# eBox_Led.net
KiCad netlist of a schematic drawn in Altium Designer
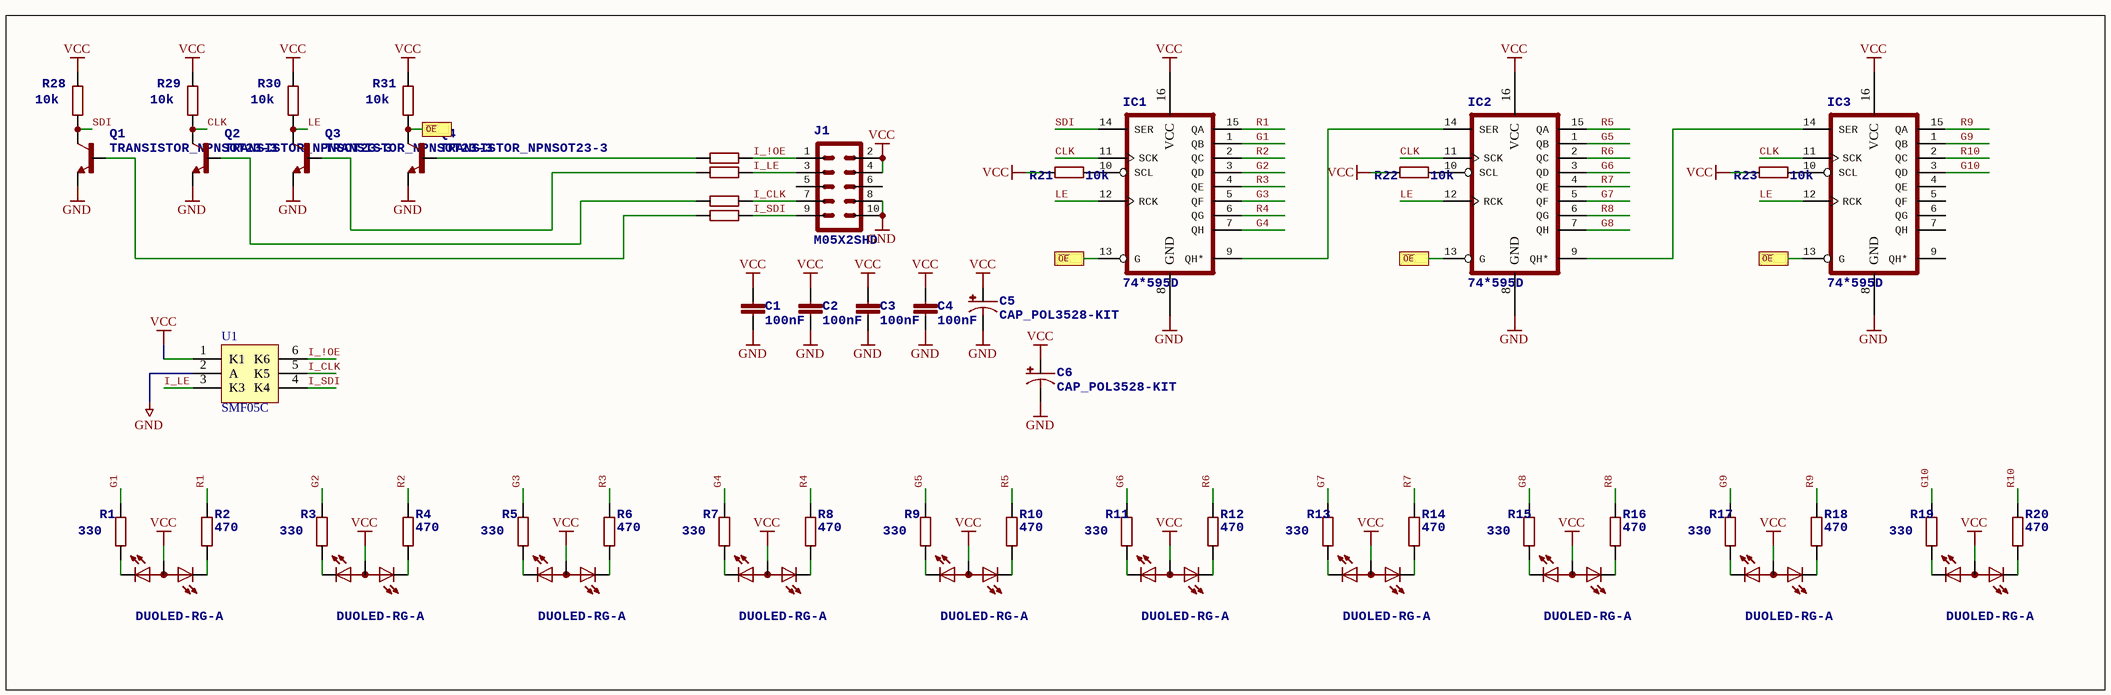
[diagram p0: eBox_Led.SchDoc]

(export (version "E")
  (design (tool "Eeschema 10.0.6"))
  (components
    (comp (ref "C1")
      (value "100nF")
      (footprint "C 0603")
      (description "CapacitorStandard 0603 ceramic capacitor, and 0.1\" leaded capacitor.")
      (libsource (lib "SparkFun-Capacitors") (part "CAP0603-CAP"))
    )
    (comp (ref "C2")
      (value "100nF")
      (footprint "C 0603")
      (description "CapacitorStandard 0603 ceramic capacitor, and 0.1\" leaded capacitor.")
      (libsource (lib "SparkFun-Capacitors") (part "CAP0603-CAP"))
    )
    (comp (ref "C3")
      (value "100nF")
      (footprint "C 0603")
      (description "CapacitorStandard 0603 ceramic capacitor, and 0.1\" leaded capacitor.")
      (libsource (lib "SparkFun-Capacitors") (part "CAP0603-CAP"))
    )
    (comp (ref "C4")
      (value "100nF")
      (footprint "C 0603")
      (description "CapacitorStandard 0603 ceramic capacitor, and 0.1\" leaded capacitor.")
      (libsource (lib "SparkFun-Capacitors") (part "CAP0603-CAP"))
    )
    (comp (ref "C5")
      (value "CAP_POL3528-KIT")
      (footprint "CYL/D.250/LS.100")
      (libsource (lib "SparkFun-Passives") (part "CAP_POL3528-KIT"))
    )
    (comp (ref "C6")
      (value "CAP_POL3528-KIT")
      (footprint "CYL/D.250/LS.100")
      (libsource (lib "SparkFun-Passives") (part "CAP_POL3528-KIT"))
    )
    (comp (ref "IC1")
      (value "74*595D")
      (footprint "SOIC-16")
      (description "8-bit SHIFT REGISTER, output latch")
      (libsource (lib "74xx-eu") (part "74*595D"))
    )
    (comp (ref "IC2")
      (value "74*595D")
      (footprint "SOIC-16")
      (description "8-bit SHIFT REGISTER, output latch")
      (libsource (lib "74xx-eu") (part "74*595D"))
    )
    (comp (ref "IC3")
      (value "74*595D")
      (footprint "SOIC-16")
      (description "8-bit SHIFT REGISTER, output latch")
      (libsource (lib "74xx-eu") (part "74*595D"))
    )
    (comp (ref "J1")
      (value "M05X2SHD")
      (footprint "2X5-SHROUDED")
      (libsource (lib "SparkFun-Connectors") (part "M05X2SHD"))
    )
    (comp (ref "LD1")
      (value "DUOLED-RG-A")
      (footprint "DUOLED-A-5MM")
      (description "DUO LED   2 colors (red/green), 5 mm, round, common Anode www.ligitek.com or other producers.")
      (libsource (lib "led") (part "DUOLED-RG-A"))
    )
    (comp (ref "LD2")
      (value "DUOLED-RG-A")
      (footprint "DUOLED-A-5MM")
      (description "DUO LED   2 colors (red/green), 5 mm, round, common Anode www.ligitek.com or other producers.")
      (libsource (lib "led") (part "DUOLED-RG-A"))
    )
    (comp (ref "LD3")
      (value "DUOLED-RG-A")
      (footprint "DUOLED-A-5MM")
      (description "DUO LED   2 colors (red/green), 5 mm, round, common Anode www.ligitek.com or other producers.")
      (libsource (lib "led") (part "DUOLED-RG-A"))
    )
    (comp (ref "LD4")
      (value "DUOLED-RG-A")
      (footprint "DUOLED-A-5MM")
      (description "DUO LED   2 colors (red/green), 5 mm, round, common Anode www.ligitek.com or other producers.")
      (libsource (lib "led") (part "DUOLED-RG-A"))
    )
    (comp (ref "LD5")
      (value "DUOLED-RG-A")
      (footprint "DUOLED-A-5MM")
      (description "DUO LED   2 colors (red/green), 5 mm, round, common Anode www.ligitek.com or other producers.")
      (libsource (lib "led") (part "DUOLED-RG-A"))
    )
    (comp (ref "LD6")
      (value "DUOLED-RG-A")
      (footprint "DUOLED-A-5MM")
      (description "DUO LED   2 colors (red/green), 5 mm, round, common Anode www.ligitek.com or other producers.")
      (libsource (lib "led") (part "DUOLED-RG-A"))
    )
    (comp (ref "LD7")
      (value "DUOLED-RG-A")
      (footprint "DUOLED-A-5MM")
      (description "DUO LED   2 colors (red/green), 5 mm, round, common Anode www.ligitek.com or other producers.")
      (libsource (lib "led") (part "DUOLED-RG-A"))
    )
    (comp (ref "LD8")
      (value "DUOLED-RG-A")
      (footprint "DUOLED-A-5MM")
      (description "DUO LED   2 colors (red/green), 5 mm, round, common Anode www.ligitek.com or other producers.")
      (libsource (lib "led") (part "DUOLED-RG-A"))
    )
    (comp (ref "LD9")
      (value "DUOLED-RG-A")
      (footprint "DUOLED-A-5MM")
      (description "DUO LED   2 colors (red/green), 5 mm, round, common Anode www.ligitek.com or other producers.")
      (libsource (lib "led") (part "DUOLED-RG-A"))
    )
    (comp (ref "LD10")
      (value "DUOLED-RG-A")
      (footprint "DUOLED-A-5MM")
      (description "DUO LED   2 colors (red/green), 5 mm, round, common Anode www.ligitek.com or other producers.")
      (libsource (lib "led") (part "DUOLED-RG-A"))
    )
    (comp (ref "Q1")
      (value "TRANSISTOR_NPNSOT23-3")
      (footprint "SOT23-3")
      (libsource (lib "SparkFun-DiscreteSemi") (part "TRANSISTOR_NPNSOT23-3"))
    )
    (comp (ref "Q2")
      (value "TRANSISTOR_NPNSOT23-3")
      (footprint "SOT23-3")
      (libsource (lib "SparkFun-DiscreteSemi") (part "TRANSISTOR_NPNSOT23-3"))
    )
    (comp (ref "Q3")
      (value "TRANSISTOR_NPNSOT23-3")
      (footprint "SOT23-3")
      (libsource (lib "SparkFun-DiscreteSemi") (part "TRANSISTOR_NPNSOT23-3"))
    )
    (comp (ref "Q4")
      (value "TRANSISTOR_NPNSOT23-3")
      (footprint "SOT23-3")
      (libsource (lib "SparkFun-DiscreteSemi") (part "TRANSISTOR_NPNSOT23-3"))
    )
    (comp (ref "R1")
      (value "330")
      (footprint "R 0603")
      (description "RESISTOR, European symbol")
      (libsource (lib "rcl") (part "R-EU_R0603"))
    )
    (comp (ref "R2")
      (value "470")
      (footprint "R 0603")
      (description "RESISTOR, European symbol")
      (libsource (lib "rcl") (part "R-EU_R0603"))
    )
    (comp (ref "R3")
      (value "330")
      (footprint "R 0603")
      (description "RESISTOR, European symbol")
      (libsource (lib "rcl") (part "R-EU_R0603"))
    )
    (comp (ref "R4")
      (value "470")
      (footprint "R 0603")
      (description "RESISTOR, European symbol")
      (libsource (lib "rcl") (part "R-EU_R0603"))
    )
    (comp (ref "R5")
      (value "330")
      (footprint "R 0603")
      (description "RESISTOR, European symbol")
      (libsource (lib "rcl") (part "R-EU_R0603"))
    )
    (comp (ref "R6")
      (value "470")
      (footprint "R 0603")
      (description "RESISTOR, European symbol")
      (libsource (lib "rcl") (part "R-EU_R0603"))
    )
    (comp (ref "R7")
      (value "330")
      (footprint "R 0603")
      (description "RESISTOR, European symbol")
      (libsource (lib "rcl") (part "R-EU_R0603"))
    )
    (comp (ref "R8")
      (value "470")
      (footprint "R 0603")
      (description "RESISTOR, European symbol")
      (libsource (lib "rcl") (part "R-EU_R0603"))
    )
    (comp (ref "R9")
      (value "330")
      (footprint "R 0603")
      (description "RESISTOR, European symbol")
      (libsource (lib "rcl") (part "R-EU_R0603"))
    )
    (comp (ref "R10")
      (value "470")
      (footprint "R 0603")
      (description "RESISTOR, European symbol")
      (libsource (lib "rcl") (part "R-EU_R0603"))
    )
    (comp (ref "R11")
      (value "330")
      (footprint "R 0603")
      (description "RESISTOR, European symbol")
      (libsource (lib "rcl") (part "R-EU_R0603"))
    )
    (comp (ref "R12")
      (value "470")
      (footprint "R 0603")
      (description "RESISTOR, European symbol")
      (libsource (lib "rcl") (part "R-EU_R0603"))
    )
    (comp (ref "R13")
      (value "330")
      (footprint "R 0603")
      (description "RESISTOR, European symbol")
      (libsource (lib "rcl") (part "R-EU_R0603"))
    )
    (comp (ref "R14")
      (value "470")
      (footprint "R 0603")
      (description "RESISTOR, European symbol")
      (libsource (lib "rcl") (part "R-EU_R0603"))
    )
    (comp (ref "R15")
      (value "330")
      (footprint "R 0603")
      (description "RESISTOR, European symbol")
      (libsource (lib "rcl") (part "R-EU_R0603"))
    )
    (comp (ref "R16")
      (value "470")
      (footprint "R 0603")
      (description "RESISTOR, European symbol")
      (libsource (lib "rcl") (part "R-EU_R0603"))
    )
    (comp (ref "R17")
      (value "330")
      (footprint "R 0603")
      (description "RESISTOR, European symbol")
      (libsource (lib "rcl") (part "R-EU_R0603"))
    )
    (comp (ref "R18")
      (value "470")
      (footprint "R 0603")
      (description "RESISTOR, European symbol")
      (libsource (lib "rcl") (part "R-EU_R0603"))
    )
    (comp (ref "R19")
      (value "330")
      (footprint "R 0603")
      (description "RESISTOR, European symbol")
      (libsource (lib "rcl") (part "R-EU_R0603"))
    )
    (comp (ref "R20")
      (value "470")
      (footprint "R 0603")
      (description "RESISTOR, European symbol")
      (libsource (lib "rcl") (part "R-EU_R0603"))
    )
    (comp (ref "R21")
      (value "10k")
      (footprint "R 0603")
      (description "RESISTOR, European symbol")
      (libsource (lib "rcl") (part "R-EU_R0603"))
    )
    (comp (ref "R22")
      (value "10k")
      (footprint "R 0603")
      (description "RESISTOR, European symbol")
      (libsource (lib "rcl") (part "R-EU_R0603"))
    )
    (comp (ref "R23")
      (value "10k")
      (footprint "R 0603")
      (description "RESISTOR, European symbol")
      (libsource (lib "rcl") (part "R-EU_R0603"))
    )
    (comp (ref "R24")
      (value "10k")
      (footprint "R 0603")
      (description "RESISTOR, European symbol")
      (libsource (lib "rcl") (part "R-EU_R0603"))
    )
    (comp (ref "R25")
      (value "10k")
      (footprint "R 0603")
      (description "RESISTOR, European symbol")
      (libsource (lib "rcl") (part "R-EU_R0603"))
    )
    (comp (ref "R26")
      (value "10k")
      (footprint "R 0603")
      (description "RESISTOR, European symbol")
      (libsource (lib "rcl") (part "R-EU_R0603"))
    )
    (comp (ref "R27")
      (value "10k")
      (footprint "R 0603")
      (description "RESISTOR, European symbol")
      (libsource (lib "rcl") (part "R-EU_R0603"))
    )
    (comp (ref "R28")
      (value "10k")
      (footprint "R 0603")
      (description "RESISTOR, European symbol")
      (libsource (lib "rcl") (part "R-EU_R0603"))
    )
    (comp (ref "R29")
      (value "10k")
      (footprint "R 0603")
      (description "RESISTOR, European symbol")
      (libsource (lib "rcl") (part "R-EU_R0603"))
    )
    (comp (ref "R30")
      (value "10k")
      (footprint "R 0603")
      (description "RESISTOR, European symbol")
      (libsource (lib "rcl") (part "R-EU_R0603"))
    )
    (comp (ref "R31")
      (value "10k")
      (footprint "R 0603")
      (description "RESISTOR, European symbol")
      (libsource (lib "rcl") (part "R-EU_R0603"))
    )
    (comp (ref "U1")
      (value "SMF05C")
      (footprint "SOT-363-6")
      (description "5-Line Transient Voltage Suppressor Array")
      (libsource (lib "common_altium_libs") (part "SMF05C"))
    )
  )
  (nets
    (net (code "1") (name "/CLK") (class "Default")
      (node (ref "IC1") (pin "11") (pinfunction "SCK_11") (pintype "passive"))
      (node (ref "IC2") (pin "11") (pinfunction "SCK_11") (pintype "passive"))
      (node (ref "IC3") (pin "11") (pinfunction "SCK_11") (pintype "passive"))
      (node (ref "Q2") (pin "3") (pinfunction "C_3") (pintype "passive"))
      (node (ref "R29") (pin "1") (pinfunction "1_1") (pintype "passive"))
    )
    (net (code "2") (name "/G1") (class "Default")
      (node (ref "IC1") (pin "1") (pinfunction "QB_1") (pintype "tri_state"))
      (node (ref "R1") (pin "2") (pinfunction "2_2") (pintype "passive"))
    )
    (net (code "3") (name "/G2") (class "Default")
      (node (ref "IC1") (pin "3") (pinfunction "QD_3") (pintype "tri_state"))
      (node (ref "R3") (pin "2") (pinfunction "2_2") (pintype "passive"))
    )
    (net (code "4") (name "/G3") (class "Default")
      (node (ref "IC1") (pin "5") (pinfunction "QF_5") (pintype "tri_state"))
      (node (ref "R5") (pin "2") (pinfunction "2_2") (pintype "passive"))
    )
    (net (code "5") (name "/G4") (class "Default")
      (node (ref "IC1") (pin "7") (pinfunction "QH_7") (pintype "tri_state"))
      (node (ref "R7") (pin "2") (pinfunction "2_2") (pintype "passive"))
    )
    (net (code "6") (name "/G5") (class "Default")
      (node (ref "IC2") (pin "1") (pinfunction "QB_1") (pintype "tri_state"))
      (node (ref "R9") (pin "2") (pinfunction "2_2") (pintype "passive"))
    )
    (net (code "7") (name "/G6") (class "Default")
      (node (ref "IC2") (pin "3") (pinfunction "QD_3") (pintype "tri_state"))
      (node (ref "R11") (pin "2") (pinfunction "2_2") (pintype "passive"))
    )
    (net (code "8") (name "/G7") (class "Default")
      (node (ref "IC2") (pin "5") (pinfunction "QF_5") (pintype "tri_state"))
      (node (ref "R13") (pin "2") (pinfunction "2_2") (pintype "passive"))
    )
    (net (code "9") (name "/G8") (class "Default")
      (node (ref "IC2") (pin "7") (pinfunction "QH_7") (pintype "tri_state"))
      (node (ref "R15") (pin "2") (pinfunction "2_2") (pintype "passive"))
    )
    (net (code "10") (name "/G9") (class "Default")
      (node (ref "IC3") (pin "1") (pinfunction "QB_1") (pintype "tri_state"))
      (node (ref "R17") (pin "2") (pinfunction "2_2") (pintype "passive"))
    )
    (net (code "11") (name "/G10") (class "Default")
      (node (ref "IC3") (pin "3") (pinfunction "QD_3") (pintype "tri_state"))
      (node (ref "R19") (pin "2") (pinfunction "2_2") (pintype "passive"))
    )
    (net (code "12") (name "/I_!OE") (class "Default")
      (node (ref "J1") (pin "1") (pinfunction "1_1") (pintype "passive"))
      (node (ref "R24") (pin "1") (pinfunction "1_1") (pintype "passive"))
      (node (ref "U1") (pin "6") (pinfunction "K6_6") (pintype "passive"))
    )
    (net (code "13") (name "/I_CLK") (class "Default")
      (node (ref "J1") (pin "7") (pinfunction "7_7") (pintype "passive"))
      (node (ref "R26") (pin "1") (pinfunction "1_1") (pintype "passive"))
      (node (ref "U1") (pin "5") (pinfunction "K5_5") (pintype "passive"))
    )
    (net (code "14") (name "/I_LE") (class "Default")
      (node (ref "J1") (pin "3") (pinfunction "3_3") (pintype "passive"))
      (node (ref "R25") (pin "1") (pinfunction "1_1") (pintype "passive"))
      (node (ref "U1") (pin "3") (pinfunction "K3_3") (pintype "passive"))
    )
    (net (code "15") (name "/I_SDI") (class "Default")
      (node (ref "J1") (pin "9") (pinfunction "9_9") (pintype "passive"))
      (node (ref "R27") (pin "1") (pinfunction "1_1") (pintype "passive"))
      (node (ref "U1") (pin "4") (pinfunction "K4_4") (pintype "passive"))
    )
    (net (code "16") (name "/LE") (class "Default")
      (node (ref "IC1") (pin "12") (pinfunction "RCK_12") (pintype "passive"))
      (node (ref "IC2") (pin "12") (pinfunction "RCK_12") (pintype "passive"))
      (node (ref "IC3") (pin "12") (pinfunction "RCK_12") (pintype "passive"))
      (node (ref "Q3") (pin "3") (pinfunction "C_3") (pintype "passive"))
      (node (ref "R30") (pin "1") (pinfunction "1_1") (pintype "passive"))
    )
    (net (code "17") (name "/R1") (class "Default")
      (node (ref "IC1") (pin "15") (pinfunction "QA_15") (pintype "tri_state"))
      (node (ref "R2") (pin "2") (pinfunction "2_2") (pintype "passive"))
    )
    (net (code "18") (name "/R2") (class "Default")
      (node (ref "IC1") (pin "2") (pinfunction "QC_2") (pintype "tri_state"))
      (node (ref "R4") (pin "2") (pinfunction "2_2") (pintype "passive"))
    )
    (net (code "19") (name "/R3") (class "Default")
      (node (ref "IC1") (pin "4") (pinfunction "QE_4") (pintype "tri_state"))
      (node (ref "R6") (pin "2") (pinfunction "2_2") (pintype "passive"))
    )
    (net (code "20") (name "/R4") (class "Default")
      (node (ref "IC1") (pin "6") (pinfunction "QG_6") (pintype "tri_state"))
      (node (ref "R8") (pin "2") (pinfunction "2_2") (pintype "passive"))
    )
    (net (code "21") (name "/R5") (class "Default")
      (node (ref "IC2") (pin "15") (pinfunction "QA_15") (pintype "tri_state"))
      (node (ref "R10") (pin "2") (pinfunction "2_2") (pintype "passive"))
    )
    (net (code "22") (name "/R6") (class "Default")
      (node (ref "IC2") (pin "2") (pinfunction "QC_2") (pintype "tri_state"))
      (node (ref "R12") (pin "2") (pinfunction "2_2") (pintype "passive"))
    )
    (net (code "23") (name "/R7") (class "Default")
      (node (ref "IC2") (pin "4") (pinfunction "QE_4") (pintype "tri_state"))
      (node (ref "R14") (pin "2") (pinfunction "2_2") (pintype "passive"))
    )
    (net (code "24") (name "/R8") (class "Default")
      (node (ref "IC2") (pin "6") (pinfunction "QG_6") (pintype "tri_state"))
      (node (ref "R16") (pin "2") (pinfunction "2_2") (pintype "passive"))
    )
    (net (code "25") (name "/R9") (class "Default")
      (node (ref "IC3") (pin "15") (pinfunction "QA_15") (pintype "tri_state"))
      (node (ref "R18") (pin "2") (pinfunction "2_2") (pintype "passive"))
    )
    (net (code "26") (name "/R10") (class "Default")
      (node (ref "IC3") (pin "2") (pinfunction "QC_2") (pintype "tri_state"))
      (node (ref "R20") (pin "2") (pinfunction "2_2") (pintype "passive"))
    )
    (net (code "27") (name "/SDI") (class "Default")
      (node (ref "IC1") (pin "14") (pinfunction "SER_14") (pintype "passive"))
      (node (ref "Q1") (pin "3") (pinfunction "C_3") (pintype "passive"))
      (node (ref "R28") (pin "1") (pinfunction "1_1") (pintype "passive"))
    )
    (net (code "28") (name "/~{OE}") (class "Default")
      (node (ref "IC1") (pin "13") (pinfunction "G_13") (pintype "passive"))
      (node (ref "IC2") (pin "13") (pinfunction "G_13") (pintype "passive"))
      (node (ref "IC3") (pin "13") (pinfunction "G_13") (pintype "passive"))
      (node (ref "Q4") (pin "3") (pinfunction "C_3") (pintype "passive"))
      (node (ref "R31") (pin "1") (pinfunction "1_1") (pintype "passive"))
    )
    (net (code "29") (name "GND") (class "Default")
      (node (ref "C1") (pin "2") (pinfunction "2_2") (pintype "passive"))
      (node (ref "C2") (pin "2") (pinfunction "2_2") (pintype "passive"))
      (node (ref "C3") (pin "2") (pinfunction "2_2") (pintype "passive"))
      (node (ref "C4") (pin "2") (pinfunction "2_2") (pintype "passive"))
      (node (ref "C5") (pin "2") (pinfunction "-_2") (pintype "passive"))
      (node (ref "C6") (pin "2") (pinfunction "-_2") (pintype "passive"))
      (node (ref "IC1") (pin "8") (pinfunction "GND_8") (pintype "passive"))
      (node (ref "IC2") (pin "8") (pinfunction "GND_8") (pintype "passive"))
      (node (ref "IC3") (pin "8") (pinfunction "GND_8") (pintype "passive"))
      (node (ref "J1") (pin "10") (pinfunction "10_10") (pintype "passive"))
      (node (ref "J1") (pin "8") (pinfunction "8_8") (pintype "passive"))
      (node (ref "Q1") (pin "2") (pinfunction "E_2") (pintype "passive"))
      (node (ref "Q2") (pin "2") (pinfunction "E_2") (pintype "passive"))
      (node (ref "Q3") (pin "2") (pinfunction "E_2") (pintype "passive"))
      (node (ref "Q4") (pin "2") (pinfunction "E_2") (pintype "passive"))
      (node (ref "U1") (pin "2") (pinfunction "A_2") (pintype "passive"))
    )
    (net (code "30") (name "Net-(IC1-QH*)") (class "Default")
      (node (ref "IC1") (pin "9") (pinfunction "QH*_9") (pintype "tri_state"))
      (node (ref "IC2") (pin "14") (pinfunction "SER_14") (pintype "passive"))
    )
    (net (code "31") (name "Net-(IC1-SCL)") (class "Default")
      (node (ref "IC1") (pin "10") (pinfunction "SCL_10") (pintype "passive"))
      (node (ref "R21") (pin "1") (pinfunction "1_1") (pintype "passive"))
    )
    (net (code "32") (name "Net-(IC2-QH*)") (class "Default")
      (node (ref "IC2") (pin "9") (pinfunction "QH*_9") (pintype "tri_state"))
      (node (ref "IC3") (pin "14") (pinfunction "SER_14") (pintype "passive"))
    )
    (net (code "33") (name "Net-(IC2-SCL)") (class "Default")
      (node (ref "IC2") (pin "10") (pinfunction "SCL_10") (pintype "passive"))
      (node (ref "R22") (pin "1") (pinfunction "1_1") (pintype "passive"))
    )
    (net (code "34") (name "Net-(IC3-SCL)") (class "Default")
      (node (ref "IC3") (pin "10") (pinfunction "SCL_10") (pintype "passive"))
      (node (ref "R23") (pin "1") (pinfunction "1_1") (pintype "passive"))
    )
    (net (code "35") (name "Net-(LD1-CG)") (class "Default")
      (node (ref "LD1") (pin "CX") (pinfunction "CG_CX") (pintype "passive"))
      (node (ref "R1") (pin "1") (pinfunction "1_1") (pintype "passive"))
    )
    (net (code "36") (name "Net-(LD1-PadCR)") (class "Default")
      (node (ref "LD1") (pin "CR") (pinfunction "CR_CR") (pintype "passive"))
      (node (ref "R2") (pin "1") (pinfunction "1_1") (pintype "passive"))
    )
    (net (code "37") (name "Net-(LD2-CG)") (class "Default")
      (node (ref "LD2") (pin "CX") (pinfunction "CG_CX") (pintype "passive"))
      (node (ref "R3") (pin "1") (pinfunction "1_1") (pintype "passive"))
    )
    (net (code "38") (name "Net-(LD2-PadCR)") (class "Default")
      (node (ref "LD2") (pin "CR") (pinfunction "CR_CR") (pintype "passive"))
      (node (ref "R4") (pin "1") (pinfunction "1_1") (pintype "passive"))
    )
    (net (code "39") (name "Net-(LD3-CG)") (class "Default")
      (node (ref "LD3") (pin "CX") (pinfunction "CG_CX") (pintype "passive"))
      (node (ref "R5") (pin "1") (pinfunction "1_1") (pintype "passive"))
    )
    (net (code "40") (name "Net-(LD3-PadCR)") (class "Default")
      (node (ref "LD3") (pin "CR") (pinfunction "CR_CR") (pintype "passive"))
      (node (ref "R6") (pin "1") (pinfunction "1_1") (pintype "passive"))
    )
    (net (code "41") (name "Net-(LD4-CG)") (class "Default")
      (node (ref "LD4") (pin "CX") (pinfunction "CG_CX") (pintype "passive"))
      (node (ref "R7") (pin "1") (pinfunction "1_1") (pintype "passive"))
    )
    (net (code "42") (name "Net-(LD4-PadCR)") (class "Default")
      (node (ref "LD4") (pin "CR") (pinfunction "CR_CR") (pintype "passive"))
      (node (ref "R8") (pin "1") (pinfunction "1_1") (pintype "passive"))
    )
    (net (code "43") (name "Net-(LD5-CG)") (class "Default")
      (node (ref "LD5") (pin "CX") (pinfunction "CG_CX") (pintype "passive"))
      (node (ref "R9") (pin "1") (pinfunction "1_1") (pintype "passive"))
    )
    (net (code "44") (name "Net-(LD5-PadCR)") (class "Default")
      (node (ref "LD5") (pin "CR") (pinfunction "CR_CR") (pintype "passive"))
      (node (ref "R10") (pin "1") (pinfunction "1_1") (pintype "passive"))
    )
    (net (code "45") (name "Net-(LD6-CG)") (class "Default")
      (node (ref "LD6") (pin "CX") (pinfunction "CG_CX") (pintype "passive"))
      (node (ref "R11") (pin "1") (pinfunction "1_1") (pintype "passive"))
    )
    (net (code "46") (name "Net-(LD6-PadCR)") (class "Default")
      (node (ref "LD6") (pin "CR") (pinfunction "CR_CR") (pintype "passive"))
      (node (ref "R12") (pin "1") (pinfunction "1_1") (pintype "passive"))
    )
    (net (code "47") (name "Net-(LD7-CG)") (class "Default")
      (node (ref "LD7") (pin "CX") (pinfunction "CG_CX") (pintype "passive"))
      (node (ref "R13") (pin "1") (pinfunction "1_1") (pintype "passive"))
    )
    (net (code "48") (name "Net-(LD7-PadCR)") (class "Default")
      (node (ref "LD7") (pin "CR") (pinfunction "CR_CR") (pintype "passive"))
      (node (ref "R14") (pin "1") (pinfunction "1_1") (pintype "passive"))
    )
    (net (code "49") (name "Net-(LD8-CG)") (class "Default")
      (node (ref "LD8") (pin "CX") (pinfunction "CG_CX") (pintype "passive"))
      (node (ref "R15") (pin "1") (pinfunction "1_1") (pintype "passive"))
    )
    (net (code "50") (name "Net-(LD8-PadCR)") (class "Default")
      (node (ref "LD8") (pin "CR") (pinfunction "CR_CR") (pintype "passive"))
      (node (ref "R16") (pin "1") (pinfunction "1_1") (pintype "passive"))
    )
    (net (code "51") (name "Net-(LD9-CG)") (class "Default")
      (node (ref "LD9") (pin "CX") (pinfunction "CG_CX") (pintype "passive"))
      (node (ref "R17") (pin "1") (pinfunction "1_1") (pintype "passive"))
    )
    (net (code "52") (name "Net-(LD9-PadCR)") (class "Default")
      (node (ref "LD9") (pin "CR") (pinfunction "CR_CR") (pintype "passive"))
      (node (ref "R18") (pin "1") (pinfunction "1_1") (pintype "passive"))
    )
    (net (code "53") (name "Net-(LD10-CG)") (class "Default")
      (node (ref "LD10") (pin "CX") (pinfunction "CG_CX") (pintype "passive"))
      (node (ref "R19") (pin "1") (pinfunction "1_1") (pintype "passive"))
    )
    (net (code "54") (name "Net-(LD10-PadCR)") (class "Default")
      (node (ref "LD10") (pin "CR") (pinfunction "CR_CR") (pintype "passive"))
      (node (ref "R20") (pin "1") (pinfunction "1_1") (pintype "passive"))
    )
    (net (code "55") (name "Net-(Q1-B)") (class "Default")
      (node (ref "Q1") (pin "1") (pinfunction "B_1") (pintype "passive"))
      (node (ref "R27") (pin "2") (pinfunction "2_2") (pintype "passive"))
    )
    (net (code "56") (name "Net-(Q2-B)") (class "Default")
      (node (ref "Q2") (pin "1") (pinfunction "B_1") (pintype "passive"))
      (node (ref "R26") (pin "2") (pinfunction "2_2") (pintype "passive"))
    )
    (net (code "57") (name "Net-(Q3-B)") (class "Default")
      (node (ref "Q3") (pin "1") (pinfunction "B_1") (pintype "passive"))
      (node (ref "R25") (pin "2") (pinfunction "2_2") (pintype "passive"))
    )
    (net (code "58") (name "Net-(Q4-B)") (class "Default")
      (node (ref "Q4") (pin "1") (pinfunction "B_1") (pintype "passive"))
      (node (ref "R24") (pin "2") (pinfunction "2_2") (pintype "passive"))
    )
    (net (code "59") (name "VCC") (class "Default")
      (node (ref "C1") (pin "1") (pinfunction "1_1") (pintype "passive"))
      (node (ref "C2") (pin "1") (pinfunction "1_1") (pintype "passive"))
      (node (ref "C3") (pin "1") (pinfunction "1_1") (pintype "passive"))
      (node (ref "C4") (pin "1") (pinfunction "1_1") (pintype "passive"))
      (node (ref "C5") (pin "1") (pinfunction "+_1") (pintype "passive"))
      (node (ref "C6") (pin "1") (pinfunction "+_1") (pintype "passive"))
      (node (ref "IC1") (pin "16") (pinfunction "VCC_16") (pintype "passive"))
      (node (ref "IC2") (pin "16") (pinfunction "VCC_16") (pintype "passive"))
      (node (ref "IC3") (pin "16") (pinfunction "VCC_16") (pintype "passive"))
      (node (ref "J1") (pin "2") (pinfunction "2_2") (pintype "passive"))
      (node (ref "J1") (pin "4") (pinfunction "4_4") (pintype "passive"))
      (node (ref "LD1") (pin "A") (pinfunction "A_A") (pintype "passive"))
      (node (ref "LD10") (pin "A") (pinfunction "A_A") (pintype "passive"))
      (node (ref "LD2") (pin "A") (pinfunction "A_A") (pintype "passive"))
      (node (ref "LD3") (pin "A") (pinfunction "A_A") (pintype "passive"))
      (node (ref "LD4") (pin "A") (pinfunction "A_A") (pintype "passive"))
      (node (ref "LD5") (pin "A") (pinfunction "A_A") (pintype "passive"))
      (node (ref "LD6") (pin "A") (pinfunction "A_A") (pintype "passive"))
      (node (ref "LD7") (pin "A") (pinfunction "A_A") (pintype "passive"))
      (node (ref "LD8") (pin "A") (pinfunction "A_A") (pintype "passive"))
      (node (ref "LD9") (pin "A") (pinfunction "A_A") (pintype "passive"))
      (node (ref "R21") (pin "2") (pinfunction "2_2") (pintype "passive"))
      (node (ref "R22") (pin "2") (pinfunction "2_2") (pintype "passive"))
      (node (ref "R23") (pin "2") (pinfunction "2_2") (pintype "passive"))
      (node (ref "R28") (pin "2") (pinfunction "2_2") (pintype "passive"))
      (node (ref "R29") (pin "2") (pinfunction "2_2") (pintype "passive"))
      (node (ref "R30") (pin "2") (pinfunction "2_2") (pintype "passive"))
      (node (ref "R31") (pin "2") (pinfunction "2_2") (pintype "passive"))
      (node (ref "U1") (pin "1") (pinfunction "K1_1") (pintype "passive"))
    )
    (net (code "60") (name "unconnected-(IC3-QE-Pad4)") (class "Default")
      (node (ref "IC3") (pin "4") (pinfunction "QE_4") (pintype "tri_state"))
    )
    (net (code "61") (name "unconnected-(IC3-QF-Pad5)") (class "Default")
      (node (ref "IC3") (pin "5") (pinfunction "QF_5") (pintype "tri_state"))
    )
    (net (code "62") (name "unconnected-(IC3-QG-Pad6)") (class "Default")
      (node (ref "IC3") (pin "6") (pinfunction "QG_6") (pintype "tri_state"))
    )
    (net (code "63") (name "unconnected-(IC3-QH*-Pad9)") (class "Default")
      (node (ref "IC3") (pin "9") (pinfunction "QH*_9") (pintype "tri_state"))
    )
    (net (code "64") (name "unconnected-(IC3-QH-Pad7)") (class "Default")
      (node (ref "IC3") (pin "7") (pinfunction "QH_7") (pintype "tri_state"))
    )
    (net (code "65") (name "unconnected-(J1-Pad5)") (class "Default")
      (node (ref "J1") (pin "5") (pinfunction "5_5") (pintype "passive"))
    )
    (net (code "66") (name "unconnected-(J1-Pad6)") (class "Default")
      (node (ref "J1") (pin "6") (pinfunction "6_6") (pintype "passive"))
    )
  )
)
